# biertemp.net
KiCad netlist of a schematic drawn in EAGLE
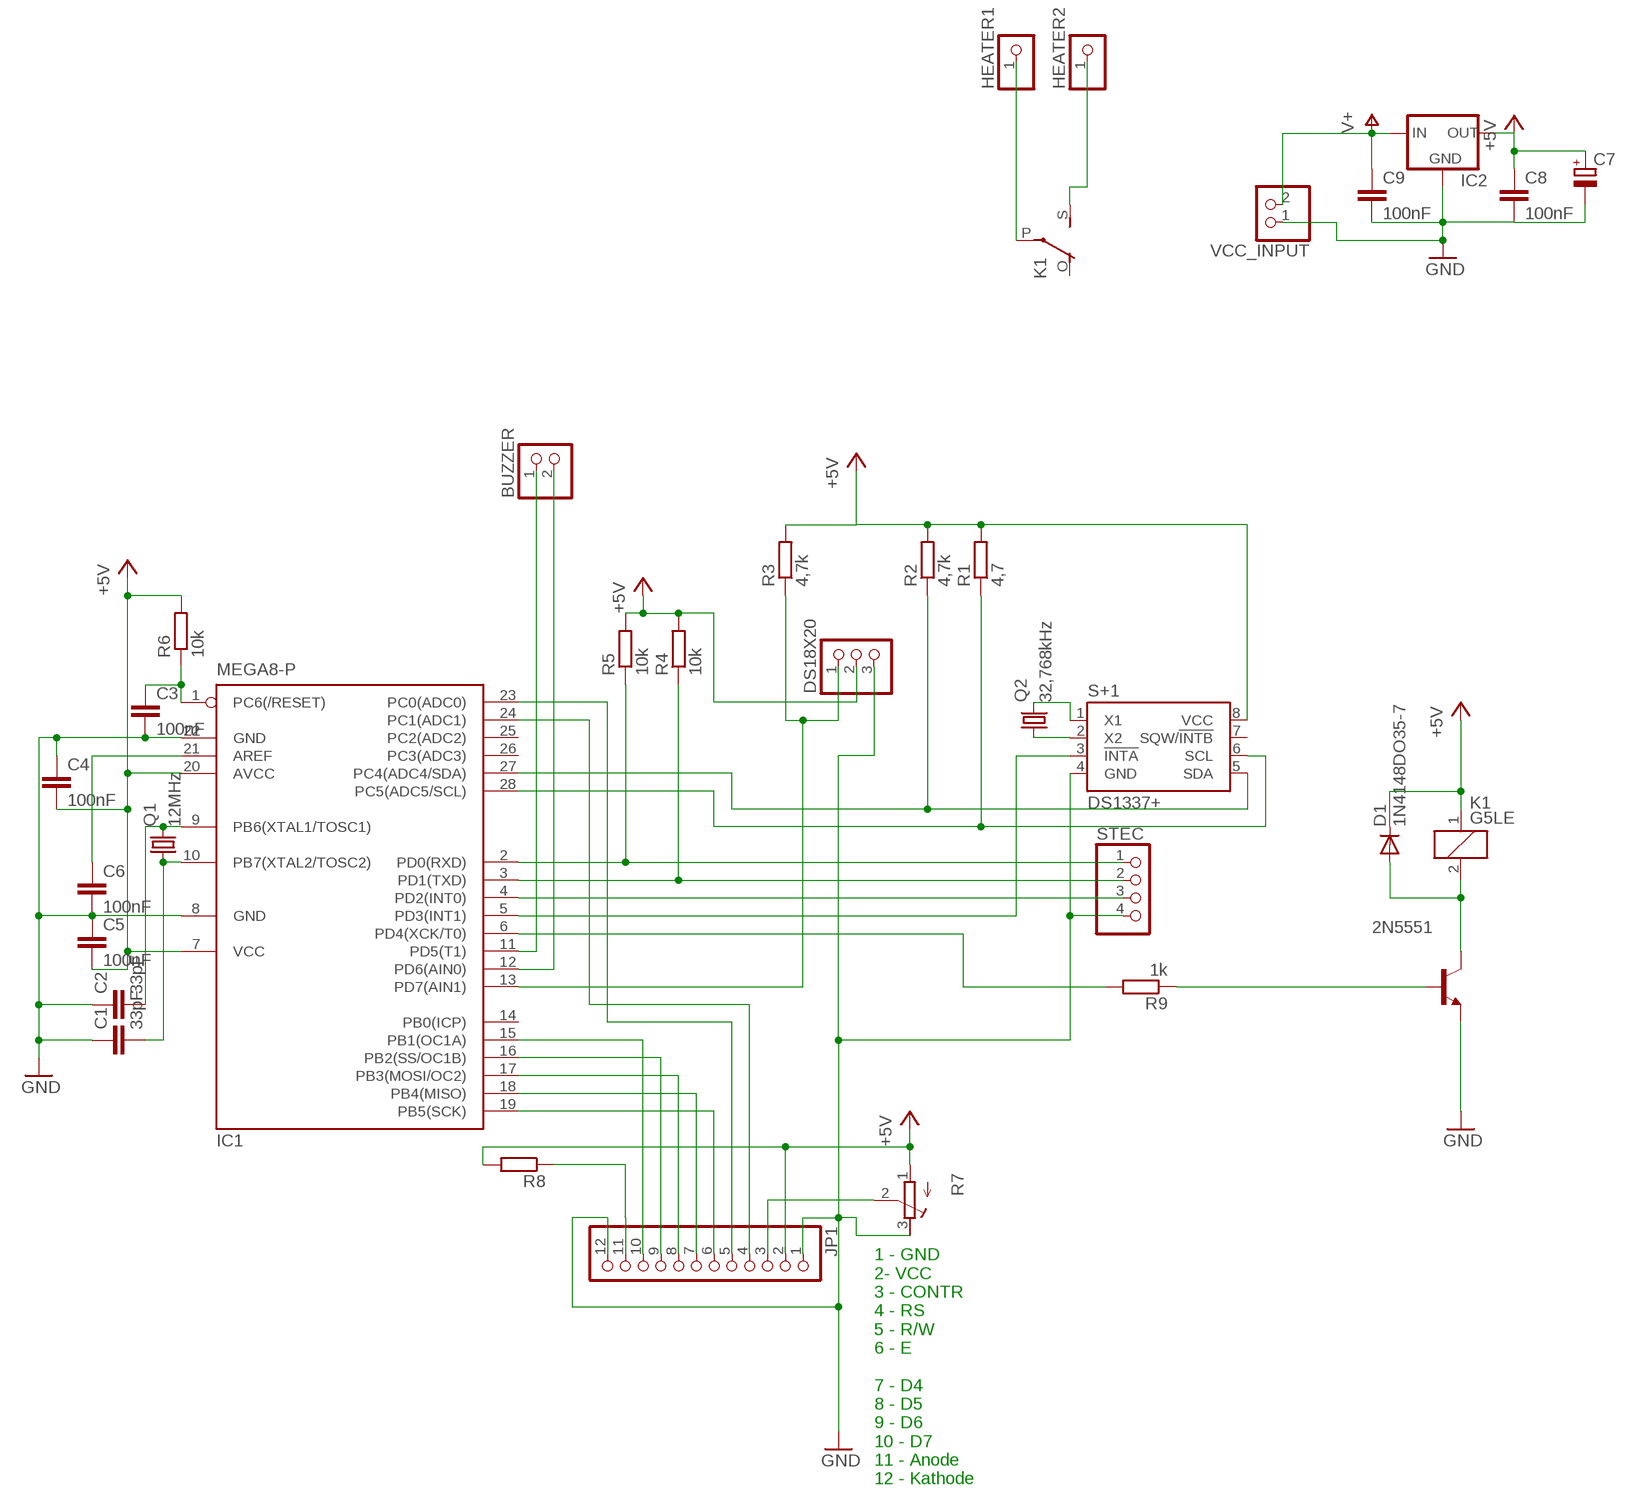
[diagram p0: schematic, sheet 1]

(export (version "E")
  (design (tool "Eeschema 10.0.6"))
  (components
    (comp (ref "2N5551")
      (value "-NPN-TO92-EBC")
      (footprint "eagle-import:TO92-EBC")
      (libsource (lib "eagle-import") (part "-NPN-TO92-EBC"))
    )
    (comp (ref "BUZZER")
      (value "PINHD-1X2")
      (footprint "eagle-import:1X02")
      (libsource (lib "eagle-import") (part "PINHD-1X2"))
    )
    (comp (ref "C1")
      (value "33pF")
      (footprint "eagle-import:C025-024X044")
      (libsource (lib "eagle-import") (part "C-EU025-024X044"))
    )
    (comp (ref "C2")
      (value "33pF")
      (footprint "eagle-import:C025-024X044")
      (libsource (lib "eagle-import") (part "C-EU025-024X044"))
    )
    (comp (ref "C3")
      (value "100nF")
      (footprint "eagle-import:C025-024X044")
      (libsource (lib "eagle-import") (part "C-EU025-024X044"))
    )
    (comp (ref "C4")
      (value "100nF")
      (footprint "eagle-import:C025-024X044")
      (libsource (lib "eagle-import") (part "C-EU025-024X044"))
    )
    (comp (ref "C5")
      (value "100nF")
      (footprint "eagle-import:C025-024X044")
      (libsource (lib "eagle-import") (part "C-EU025-024X044"))
    )
    (comp (ref "C6")
      (value "100nF")
      (footprint "eagle-import:C025-024X044")
      (libsource (lib "eagle-import") (part "C-EU025-024X044"))
    )
    (comp (ref "C7")
      (value "CPOL-EUE5-8.5")
      (footprint "eagle-import:E5-8,5")
      (libsource (lib "eagle-import") (part "CPOL-EUE5-8.5"))
    )
    (comp (ref "C8")
      (value "100nF")
      (footprint "eagle-import:C025-024X044")
      (libsource (lib "eagle-import") (part "C-EU025-024X044"))
    )
    (comp (ref "C9")
      (value "100nF")
      (footprint "eagle-import:C025-024X044")
      (libsource (lib "eagle-import") (part "C-EU025-024X044"))
    )
    (comp (ref "D1")
      (value "1N4148DO35-7")
      (footprint "eagle-import:DO35-7")
      (libsource (lib "eagle-import") (part "1N4148DO35-7"))
    )
    (comp (ref "DS18X20")
      (value "PINHD-1X3")
      (footprint "eagle-import:1X03")
      (libsource (lib "eagle-import") (part "PINHD-1X3"))
    )
    (comp (ref "HEATER1")
      (value "PINHD-1X1")
      (footprint "eagle-import:1X01")
      (libsource (lib "eagle-import") (part "PINHD-1X1"))
    )
    (comp (ref "HEATER2")
      (value "PINHD-1X1")
      (footprint "eagle-import:1X01")
      (libsource (lib "eagle-import") (part "PINHD-1X1"))
    )
    (comp (ref "IC1")
      (value "MEGA8-P")
      (footprint "eagle-import:DIL28-3")
      (libsource (lib "eagle-import") (part "MEGA8-P"))
    )
    (comp (ref "IC2")
      (value "78XXS")
      (footprint "eagle-import:78XXS")
      (libsource (lib "eagle-import") (part "78XXS"))
    )
    (comp (ref "JP1")
      (value "PINHD-1X12")
      (footprint "eagle-import:1X12")
      (libsource (lib "eagle-import") (part "PINHD-1X12"))
    )
    (comp (ref "K1")
      (value "G5LE")
      (footprint "eagle-import:G5LE")
      (libsource (lib "eagle-import") (part "G5LE"))
    )
    (comp (ref "Q1")
      (value "12MHz")
      (footprint "eagle-import:HC49_S")
      (libsource (lib "eagle-import") (part "CRYSTALHC49S"))
    )
    (comp (ref "Q2")
      (value "32,768kHz")
      (footprint "eagle-import:TC26V")
      (libsource (lib "eagle-import") (part "CRYSTALTC26V"))
    )
    (comp (ref "R1")
      (value "4,7")
      (footprint "eagle-import:0204_7")
      (libsource (lib "eagle-import") (part "R-EU_0204/7"))
    )
    (comp (ref "R2")
      (value "4,7k")
      (footprint "eagle-import:0204_7")
      (libsource (lib "eagle-import") (part "R-EU_0204/7"))
    )
    (comp (ref "R3")
      (value "4,7k")
      (footprint "eagle-import:0204_7")
      (libsource (lib "eagle-import") (part "R-EU_0204/7"))
    )
    (comp (ref "R4")
      (value "10k")
      (footprint "eagle-import:0204_7")
      (libsource (lib "eagle-import") (part "R-EU_0204/7"))
    )
    (comp (ref "R5")
      (value "10k")
      (footprint "eagle-import:0204_7")
      (libsource (lib "eagle-import") (part "R-EU_0204/7"))
    )
    (comp (ref "R6")
      (value "10k")
      (footprint "eagle-import:0204_7")
      (libsource (lib "eagle-import") (part "R-EU_0204/7"))
    )
    (comp (ref "R7")
      (value "R-TRIMM64X")
      (footprint "eagle-import:RTRIM64X")
      (libsource (lib "eagle-import") (part "R-TRIMM64X"))
    )
    (comp (ref "R8")
      (value "R-EU_0204/7")
      (footprint "eagle-import:0204_7")
      (libsource (lib "eagle-import") (part "R-EU_0204/7"))
    )
    (comp (ref "R9")
      (value "1k")
      (footprint "eagle-import:0204_7")
      (libsource (lib "eagle-import") (part "R-EU_0204/7"))
    )
    (comp (ref "S+1")
      (value "DS1337+")
      (footprint "eagle-import:DIL8")
      (libsource (lib "eagle-import") (part "DS1337+"))
    )
    (comp (ref "STEC")
      (value "PINHD-1X4")
      (footprint "eagle-import:1X04")
      (libsource (lib "eagle-import") (part "PINHD-1X4"))
    )
    (comp (ref "VCC_INPUT")
      (value "PINHD-1X2")
      (footprint "eagle-import:1X02")
      (libsource (lib "eagle-import") (part "PINHD-1X2"))
    )
  )
  (nets
    (net (code "1") (name "+5V") (class "Default")
      (node (ref "C4") (pin "2") (pinfunction "2_2") (pintype "passive"))
      (node (ref "C5") (pin "2") (pinfunction "2_2") (pintype "passive"))
      (node (ref "C7") (pin "+") (pinfunction "+_+") (pintype "passive"))
      (node (ref "C8") (pin "1") (pinfunction "1_1") (pintype "passive"))
      (node (ref "D1") (pin "C") (pinfunction "C_C") (pintype "passive"))
      (node (ref "DS18X20") (pin "2") (pinfunction "2_2") (pintype "passive"))
      (node (ref "IC1") (pin "20") (pinfunction "AVCC_20") (pintype "power_in"))
      (node (ref "IC1") (pin "7") (pinfunction "VCC_7") (pintype "power_in"))
      (node (ref "IC2") (pin "OUT") (pinfunction "OUT_OUT") (pintype "passive"))
      (node (ref "JP1") (pin "2") (pinfunction "2_2") (pintype "passive"))
      (node (ref "K1") (pin "1") (pinfunction "1_1") (pintype "passive"))
      (node (ref "R1") (pin "2") (pinfunction "2_2") (pintype "passive"))
      (node (ref "R2") (pin "2") (pinfunction "2_2") (pintype "passive"))
      (node (ref "R3") (pin "2") (pinfunction "2_2") (pintype "passive"))
      (node (ref "R4") (pin "2") (pinfunction "2_2") (pintype "passive"))
      (node (ref "R5") (pin "2") (pinfunction "2_2") (pintype "passive"))
      (node (ref "R6") (pin "2") (pinfunction "2_2") (pintype "passive"))
      (node (ref "R7") (pin "1") (pinfunction "A_1") (pintype "passive"))
      (node (ref "R8") (pin "2") (pinfunction "2_2") (pintype "passive"))
      (node (ref "S+1") (pin "8") (pinfunction "VCC_8") (pintype "bidirectional"))
    )
    (net (code "2") (name "GND") (class "Default")
      (node (ref "2N5551") (pin "E") (pinfunction "E_E") (pintype "passive"))
      (node (ref "C1") (pin "1") (pinfunction "1_1") (pintype "passive"))
      (node (ref "C2") (pin "1") (pinfunction "1_1") (pintype "passive"))
      (node (ref "C3") (pin "2") (pinfunction "2_2") (pintype "passive"))
      (node (ref "C4") (pin "1") (pinfunction "1_1") (pintype "passive"))
      (node (ref "C5") (pin "1") (pinfunction "1_1") (pintype "passive"))
      (node (ref "C6") (pin "2") (pinfunction "2_2") (pintype "passive"))
      (node (ref "C7") (pin "-") (pinfunction "-_-") (pintype "passive"))
      (node (ref "C8") (pin "2") (pinfunction "2_2") (pintype "passive"))
      (node (ref "C9") (pin "2") (pinfunction "2_2") (pintype "passive"))
      (node (ref "DS18X20") (pin "3") (pinfunction "3_3") (pintype "passive"))
      (node (ref "IC1") (pin "22") (pinfunction "GND_22") (pintype "power_in"))
      (node (ref "IC1") (pin "8") (pinfunction "GND_8") (pintype "power_in"))
      (node (ref "IC2") (pin "GND") (pinfunction "GND_GND") (pintype "input"))
      (node (ref "JP1") (pin "1") (pinfunction "1_1") (pintype "passive"))
      (node (ref "JP1") (pin "12") (pinfunction "12_12") (pintype "passive"))
      (node (ref "R7") (pin "3") (pinfunction "E_3") (pintype "passive"))
      (node (ref "S+1") (pin "4") (pinfunction "GND_4") (pintype "bidirectional"))
      (node (ref "STEC") (pin "4") (pinfunction "4_4") (pintype "passive"))
      (node (ref "VCC_INPUT") (pin "1") (pinfunction "1_1") (pintype "passive"))
    )
    (net (code "3") (name "Net-(2N5551-PadB)") (class "Default")
      (node (ref "2N5551") (pin "B") (pinfunction "B_B") (pintype "passive"))
      (node (ref "R9") (pin "1") (pinfunction "1_1") (pintype "passive"))
    )
    (net (code "4") (name "Net-(2N5551-PadC)") (class "Default")
      (node (ref "2N5551") (pin "C") (pinfunction "C_C") (pintype "passive"))
      (node (ref "D1") (pin "A") (pinfunction "A_A") (pintype "passive"))
      (node (ref "K1") (pin "2") (pinfunction "2_2") (pintype "passive"))
    )
    (net (code "5") (name "Net-(HEATER1-Pad1)") (class "Default")
      (node (ref "HEATER1") (pin "1") (pinfunction "1_1") (pintype "passive"))
      (node (ref "K1") (pin "P") (pinfunction "P_P") (pintype "passive"))
    )
    (net (code "6") (name "Net-(HEATER2-Pad1)") (class "Default")
      (node (ref "HEATER2") (pin "1") (pinfunction "1_1") (pintype "passive"))
      (node (ref "K1") (pin "S") (pinfunction "S_S") (pintype "passive"))
    )
    (net (code "7") (name "Net-(IC1-AREF)") (class "Default")
      (node (ref "C6") (pin "1") (pinfunction "1_1") (pintype "passive"))
      (node (ref "IC1") (pin "21") (pinfunction "AREF_21") (pintype "passive"))
    )
    (net (code "8") (name "Net-(IC1-PB1(OC1A))") (class "Default")
      (node (ref "IC1") (pin "15") (pinfunction "PB1(OC1A)_15") (pintype "bidirectional"))
      (node (ref "JP1") (pin "10") (pinfunction "10_10") (pintype "passive"))
    )
    (net (code "9") (name "Net-(IC1-PB2(SS{slash}OC1B))") (class "Default")
      (node (ref "IC1") (pin "16") (pinfunction "PB2(SS/OC1B)_16") (pintype "bidirectional"))
      (node (ref "JP1") (pin "9") (pinfunction "9_9") (pintype "passive"))
    )
    (net (code "10") (name "Net-(IC1-PB3(MOSI{slash}OC2))") (class "Default")
      (node (ref "IC1") (pin "17") (pinfunction "PB3(MOSI/OC2)_17") (pintype "bidirectional"))
      (node (ref "JP1") (pin "8") (pinfunction "8_8") (pintype "passive"))
    )
    (net (code "11") (name "Net-(IC1-PB4(MISO))") (class "Default")
      (node (ref "IC1") (pin "18") (pinfunction "PB4(MISO)_18") (pintype "bidirectional"))
      (node (ref "JP1") (pin "7") (pinfunction "7_7") (pintype "passive"))
    )
    (net (code "12") (name "Net-(IC1-PB5(SCK))") (class "Default")
      (node (ref "IC1") (pin "19") (pinfunction "PB5(SCK)_19") (pintype "bidirectional"))
      (node (ref "JP1") (pin "6") (pinfunction "6_6") (pintype "passive"))
    )
    (net (code "13") (name "Net-(IC1-PB6(XTAL1{slash}TOSC1))") (class "Default")
      (node (ref "C2") (pin "2") (pinfunction "2_2") (pintype "passive"))
      (node (ref "IC1") (pin "9") (pinfunction "PB6(XTAL1/TOSC1)_9") (pintype "bidirectional"))
      (node (ref "Q1") (pin "2") (pinfunction "2_2") (pintype "passive"))
    )
    (net (code "14") (name "Net-(IC1-PB7(XTAL2{slash}TOSC2))") (class "Default")
      (node (ref "C1") (pin "2") (pinfunction "2_2") (pintype "passive"))
      (node (ref "IC1") (pin "10") (pinfunction "PB7(XTAL2/TOSC2)_10") (pintype "bidirectional"))
      (node (ref "Q1") (pin "1") (pinfunction "1_1") (pintype "passive"))
    )
    (net (code "15") (name "Net-(IC1-PC0(ADC0))") (class "Default")
      (node (ref "IC1") (pin "23") (pinfunction "PC0(ADC0)_23") (pintype "bidirectional"))
      (node (ref "JP1") (pin "5") (pinfunction "5_5") (pintype "passive"))
    )
    (net (code "16") (name "Net-(IC1-PC1(ADC1))") (class "Default")
      (node (ref "IC1") (pin "24") (pinfunction "PC1(ADC1)_24") (pintype "bidirectional"))
      (node (ref "JP1") (pin "4") (pinfunction "4_4") (pintype "passive"))
    )
    (net (code "17") (name "Net-(IC1-PC4(ADC4{slash}SDA))") (class "Default")
      (node (ref "IC1") (pin "27") (pinfunction "PC4(ADC4/SDA)_27") (pintype "bidirectional"))
      (node (ref "R2") (pin "1") (pinfunction "1_1") (pintype "passive"))
      (node (ref "S+1") (pin "5") (pinfunction "SDA_5") (pintype "bidirectional"))
    )
    (net (code "18") (name "Net-(IC1-PC5(ADC5{slash}SCL))") (class "Default")
      (node (ref "IC1") (pin "28") (pinfunction "PC5(ADC5/SCL)_28") (pintype "bidirectional"))
      (node (ref "R1") (pin "1") (pinfunction "1_1") (pintype "passive"))
      (node (ref "S+1") (pin "6") (pinfunction "SCL_6") (pintype "bidirectional"))
    )
    (net (code "19") (name "Net-(IC1-PC6({slash}RESET))") (class "Default")
      (node (ref "C3") (pin "1") (pinfunction "1_1") (pintype "passive"))
      (node (ref "IC1") (pin "1") (pinfunction "PC6(/RESET)_1") (pintype "bidirectional"))
      (node (ref "R6") (pin "1") (pinfunction "1_1") (pintype "passive"))
    )
    (net (code "20") (name "Net-(IC1-PD0(RXD))") (class "Default")
      (node (ref "IC1") (pin "2") (pinfunction "PD0(RXD)_2") (pintype "bidirectional"))
      (node (ref "R5") (pin "1") (pinfunction "1_1") (pintype "passive"))
      (node (ref "STEC") (pin "1") (pinfunction "1_1") (pintype "passive"))
    )
    (net (code "21") (name "Net-(IC1-PD1(TXD))") (class "Default")
      (node (ref "IC1") (pin "3") (pinfunction "PD1(TXD)_3") (pintype "bidirectional"))
      (node (ref "R4") (pin "1") (pinfunction "1_1") (pintype "passive"))
      (node (ref "STEC") (pin "2") (pinfunction "2_2") (pintype "passive"))
    )
    (net (code "22") (name "Net-(IC1-PD2(INT0))") (class "Default")
      (node (ref "IC1") (pin "4") (pinfunction "PD2(INT0)_4") (pintype "bidirectional"))
      (node (ref "STEC") (pin "3") (pinfunction "3_3") (pintype "passive"))
    )
    (net (code "23") (name "Net-(IC1-PD3(INT1))") (class "Default")
      (node (ref "IC1") (pin "5") (pinfunction "PD3(INT1)_5") (pintype "bidirectional"))
      (node (ref "S+1") (pin "3") (pinfunction "~{INTA}_3") (pintype "bidirectional"))
    )
    (net (code "24") (name "Net-(IC1-PD4(XCK{slash}T0))") (class "Default")
      (node (ref "IC1") (pin "6") (pinfunction "PD4(XCK/T0)_6") (pintype "bidirectional"))
      (node (ref "R9") (pin "2") (pinfunction "2_2") (pintype "passive"))
    )
    (net (code "25") (name "Net-(IC1-PD5(T1))") (class "Default")
      (node (ref "BUZZER") (pin "1") (pinfunction "1_1") (pintype "passive"))
      (node (ref "IC1") (pin "11") (pinfunction "PD5(T1)_11") (pintype "bidirectional"))
    )
    (net (code "26") (name "Net-(IC1-PD6(AIN0))") (class "Default")
      (node (ref "BUZZER") (pin "2") (pinfunction "2_2") (pintype "passive"))
      (node (ref "IC1") (pin "12") (pinfunction "PD6(AIN0)_12") (pintype "bidirectional"))
    )
    (net (code "27") (name "Net-(IC1-PD7(AIN1))") (class "Default")
      (node (ref "DS18X20") (pin "1") (pinfunction "1_1") (pintype "passive"))
      (node (ref "IC1") (pin "13") (pinfunction "PD7(AIN1)_13") (pintype "bidirectional"))
      (node (ref "R3") (pin "1") (pinfunction "1_1") (pintype "passive"))
    )
    (net (code "28") (name "Net-(JP1-Pad11)") (class "Default")
      (node (ref "JP1") (pin "11") (pinfunction "11_11") (pintype "passive"))
      (node (ref "R8") (pin "1") (pinfunction "1_1") (pintype "passive"))
    )
    (net (code "29") (name "Net-(R7-S)") (class "Default")
      (node (ref "JP1") (pin "3") (pinfunction "3_3") (pintype "passive"))
      (node (ref "R7") (pin "2") (pinfunction "S_2") (pintype "passive"))
    )
    (net (code "30") (name "Net-(S+1-X1)") (class "Default")
      (node (ref "Q2") (pin "2") (pinfunction "2_2") (pintype "passive"))
      (node (ref "S+1") (pin "1") (pinfunction "X1_1") (pintype "bidirectional"))
    )
    (net (code "31") (name "Net-(S+1-X2)") (class "Default")
      (node (ref "Q2") (pin "1") (pinfunction "1_1") (pintype "passive"))
      (node (ref "S+1") (pin "2") (pinfunction "X2_2") (pintype "bidirectional"))
    )
    (net (code "32") (name "V+") (class "Default")
      (node (ref "C9") (pin "1") (pinfunction "1_1") (pintype "passive"))
      (node (ref "IC2") (pin "IN") (pinfunction "IN_IN") (pintype "input"))
      (node (ref "VCC_INPUT") (pin "2") (pinfunction "2_2") (pintype "passive"))
    )
    (net (code "33") (name "unconnected-(IC1-PB0(ICP)-Pad14)") (class "Default")
      (node (ref "IC1") (pin "14") (pinfunction "PB0(ICP)_14") (pintype "bidirectional"))
    )
    (net (code "34") (name "unconnected-(IC1-PC2(ADC2)-Pad25)") (class "Default")
      (node (ref "IC1") (pin "25") (pinfunction "PC2(ADC2)_25") (pintype "bidirectional"))
    )
    (net (code "35") (name "unconnected-(IC1-PC3(ADC3)-Pad26)") (class "Default")
      (node (ref "IC1") (pin "26") (pinfunction "PC3(ADC3)_26") (pintype "bidirectional"))
    )
    (net (code "36") (name "unconnected-(K1-PadO)") (class "Default")
      (node (ref "K1") (pin "O") (pinfunction "O_O") (pintype "passive"))
    )
    (net (code "37") (name "unconnected-(S+1-SQW{slash}~{INTB}-Pad7)") (class "Default")
      (node (ref "S+1") (pin "7") (pinfunction "SQW/~{INTB}_7") (pintype "bidirectional"))
    )
  )
)
